# PR9020.net
KiCad netlist of a schematic drawn in EAGLE
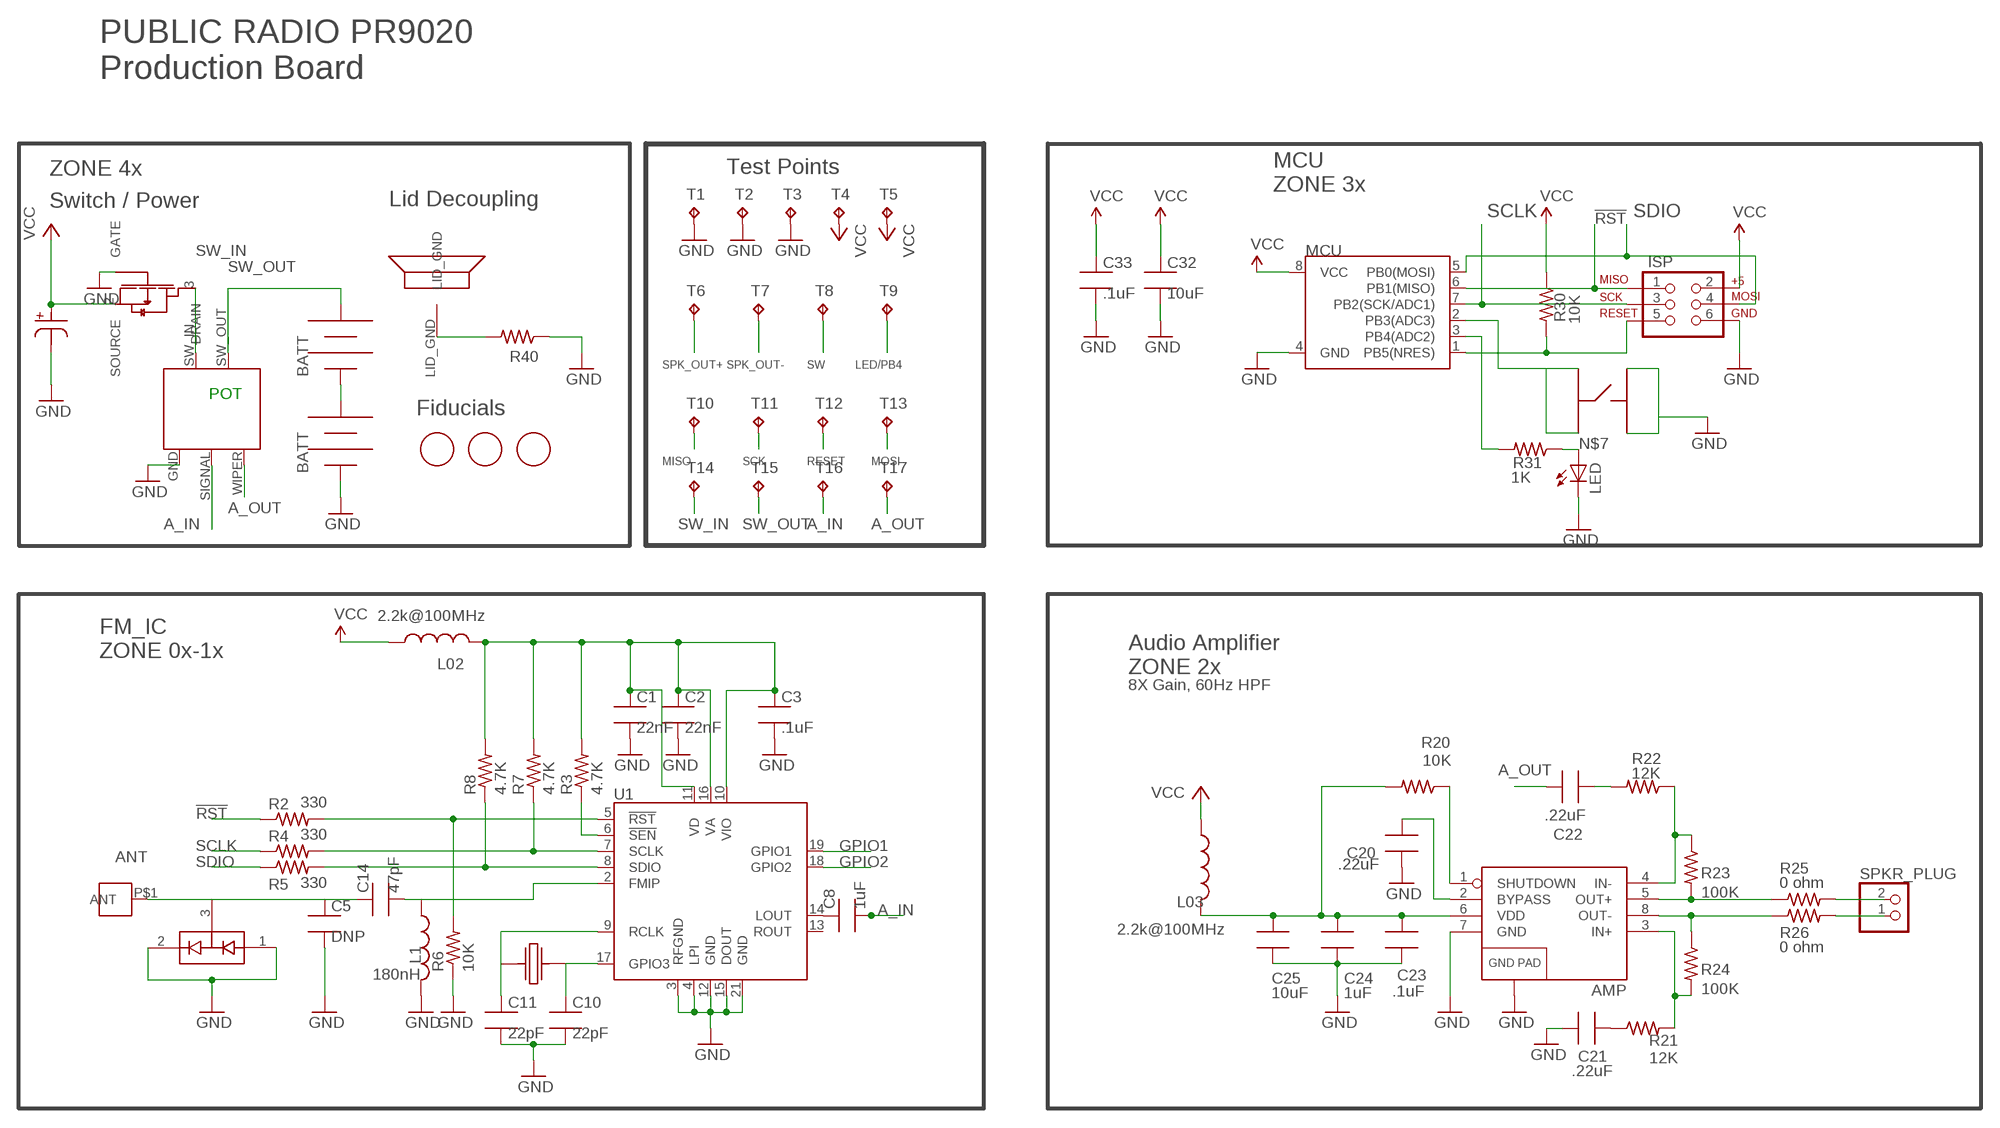
[diagram p0: schematic, sheet 1]

(export (version "E")
  (design (tool "Eeschema 10.0.6"))
  (components
    (comp (ref "AMP")
      (value "TPA6203A1")
      (footprint "eagle-import:8-MSOP")
      (libsource (lib "eagle-import") (part "TPA6203A1"))
    )
    (comp (ref "ANT_MOUNT")
      (value "DNP")
      (footprint "eagle-import:M3_BOLT_HOLE")
      (libsource (lib "eagle-import") (part "M3_SCREW_POST"))
    )
    (comp (ref "C1")
      (value "22nF")
      (footprint "eagle-import:0603_CPL")
      (fields
        (field (name "MFG_PN") "CL10B223KB8NNNC")
        (field (name "TOL") "10%")
        (field (name "VOLTAGE") "16V")
      )
      (libsource (lib "eagle-import") (part "C_SMT_0603_CPL"))
    )
    (comp (ref "C2")
      (value "22nF")
      (footprint "eagle-import:0603_CPL")
      (fields
        (field (name "MFG_PN") "CL10B223KB8NNNC")
        (field (name "TOL") "10%")
        (field (name "VOLTAGE") "16V")
      )
      (libsource (lib "eagle-import") (part "C_SMT_0603_CPL"))
    )
    (comp (ref "C3")
      (value ".1uF")
      (footprint "eagle-import:0603_CPL")
      (fields
        (field (name "MFG_PN") "CL10B104KB8SFNC")
        (field (name "TOL") "10%")
        (field (name "VOLTAGE") "16V")
      )
      (libsource (lib "eagle-import") (part "C_SMT_0603_CPL"))
    )
    (comp (ref "C5")
      (value "DNP")
      (footprint "eagle-import:0603_CPL")
      (fields (field (name "MFG_PN") "DNP") (field (name "TOL") "2%") (field (name "VOLTAGE") "50V"))
      (libsource (lib "eagle-import") (part "C_SMT_0603_CPL"))
    )
    (comp (ref "C8")
      (value "1uF")
      (footprint "eagle-import:0603_CPL")
      (fields
        (field (name "MFG_PN") "CL10B105KP8NNNC")
        (field (name "TOL") "10%")
        (field (name "VOLTAGE") "10V")
      )
      (libsource (lib "eagle-import") (part "C_SMT_0603_CPL"))
    )
    (comp (ref "C10")
      (value "22pF")
      (footprint "eagle-import:0603_CPL")
      (fields
        (field (name "MFG_PN") "C1608C0G1H220J080AA")
        (field (name "TOL") "5%")
        (field (name "VOLTAGE") "50V")
      )
      (libsource (lib "eagle-import") (part "C_SMT_0603_CPL"))
    )
    (comp (ref "C11")
      (value "22pF")
      (footprint "eagle-import:0603_CPL")
      (fields
        (field (name "MFG_PN") "C1608C0G1H220J080AA")
        (field (name "TOL") "5%")
        (field (name "VOLTAGE") "50V")
      )
      (libsource (lib "eagle-import") (part "C_SMT_0603_CPL"))
    )
    (comp (ref "C14")
      (value "47pF")
      (footprint "eagle-import:0603_CPL")
      (fields
        (field (name "MFG_PN") "CL10C470JB8NCNC")
        (field (name "TOL") "5%")
        (field (name "VOLTAGE") "50V")
      )
      (libsource (lib "eagle-import") (part "C_SMT_0603_CPL"))
    )
    (comp (ref "C20")
      (value ".22uF")
      (footprint "eagle-import:0603_CPL")
      (fields
        (field (name "MFG_PN") "C1608X7R1C224K080AC")
        (field (name "TOL") "10%")
        (field (name "VOLTAGE") "16V")
      )
      (libsource (lib "eagle-import") (part "C_SMT_0603_CPL"))
    )
    (comp (ref "C21")
      (value ".22uF")
      (footprint "eagle-import:0603_CPL")
      (fields
        (field (name "MFG_PN") "C1608X7R1C224K080AC")
        (field (name "TOL") "10%")
        (field (name "VOLTAGE") "16V")
      )
      (libsource (lib "eagle-import") (part "C_SMT_0603_CPL"))
    )
    (comp (ref "C22")
      (value ".22uF")
      (footprint "eagle-import:0603_CPL")
      (fields
        (field (name "MFG_PN") "C1608X7R1C224K080AC")
        (field (name "TOL") "10%")
        (field (name "VOLTAGE") "16V")
      )
      (libsource (lib "eagle-import") (part "C_SMT_0603_CPL"))
    )
    (comp (ref "C23")
      (value ".1uF")
      (footprint "eagle-import:0603_CPL")
      (fields
        (field (name "MFG_PN") "CL10B104KB8SFNC")
        (field (name "TOL") "10%")
        (field (name "VOLTAGE") "16V")
      )
      (libsource (lib "eagle-import") (part "C_SMT_0603_CPL"))
    )
    (comp (ref "C24")
      (value "1uF")
      (footprint "eagle-import:0603_CPL")
      (fields
        (field (name "MFG_PN") "CL10B105KP8NNNC")
        (field (name "TOL") "10%")
        (field (name "VOLTAGE") "10V")
      )
      (libsource (lib "eagle-import") (part "C_SMT_0603_CPL"))
    )
    (comp (ref "C25")
      (value "10uF")
      (footprint "eagle-import:0603_CPL")
      (fields
        (field (name "MFG_PN") "CL10A106MQ8NNNC")
        (field (name "TOL") "20%")
        (field (name "VOLTAGE") "6.3V")
      )
      (libsource (lib "eagle-import") (part "C_SMT_0603_CPL"))
    )
    (comp (ref "C32")
      (value "10uF")
      (footprint "eagle-import:0603_CPL")
      (fields
        (field (name "MFG_PN") "CL10A106MQ8NNNC")
        (field (name "TOL") "20%")
        (field (name "VOLTAGE") "6.3V")
      )
      (libsource (lib "eagle-import") (part "C_SMT_0603_CPL"))
    )
    (comp (ref "C33")
      (value ".1uF")
      (footprint "eagle-import:0603_CPL")
      (fields
        (field (name "MFG_PN") "CL10B104KB8SFNC")
        (field (name "TOL") "10%")
        (field (name "VOLTAGE") "16V")
      )
      (libsource (lib "eagle-import") (part "C_SMT_0603_CPL"))
    )
    (comp (ref "C40")
      (value "220uF")
      (footprint "eagle-import:NICHICON_UD_63")
      (fields (field (name "TOL") "20%") (field (name "VOLTAGE") "16V"))
      (libsource (lib "eagle-import") (part "NICHICON_SERIESUD"))
    )
    (comp (ref "D1")
      (value "BAV99")
      (footprint "eagle-import:SOT23_CPL")
      (fields (field (name "MFG_PN") "BAV99,215"))
      (libsource (lib "eagle-import") (part "BAV99"))
    )
    (comp (ref "FET1")
      (value "AO3435")
      (footprint "eagle-import:SOT23_CPL")
      (fields (field (name "MFG_PN") "AO3435"))
      (libsource (lib "eagle-import") (part "AO3435"))
    )
    (comp (ref "ISP")
      (value "AVR_SPI_PRG_6NS")
      (footprint "eagle-import:2X3-NS")
      (libsource (lib "eagle-import") (part "AVR_SPI_PRG_6NS"))
    )
    (comp (ref "JP5")
      (value "BK-92_MPD_AA_BATT_CLIP")
      (footprint "eagle-import:BK92_AA_BATT")
      (fields (field (name "MFG_PN") "2 of BK92 - supplied by CL Labs"))
      (libsource (lib "eagle-import") (part "BK-92_MPD_AA_BATT_CLIP"))
    )
    (comp (ref "JP6")
      (value "BK-92_MPD_AA_BATT_CLIP")
      (footprint "eagle-import:BK92_AA_BATT")
      (fields (field (name "MFG_PN") "2 of BK92 - supplied by CL Labs"))
      (libsource (lib "eagle-import") (part "BK-92_MPD_AA_BATT_CLIP"))
    )
    (comp (ref "L1")
      (value "180nH")
      (footprint "eagle-import:0805_ADAFRUIT")
      (fields
        (field (name "CURRENT") "400mA")
        (field (name "DCR") "640m")
        (field (name "MFG_PN") "AISC-0805-R18J-T")
        (field (name "TOL") "5%")
      )
      (libsource (lib "eagle-import") (part "L_SMT_0805_ADAFRUIT"))
    )
    (comp (ref "L02")
      (value "2.2k@100MHz")
      (footprint "eagle-import:0603_CPL")
      (fields
        (field (name "CURRENT") "150mA")
        (field (name "DCR") "2.3")
        (field (name "MFG_PN") "HZ0603A222R-10")
      )
      (libsource (lib "eagle-import") (part "L_SMT_0603_CPL"))
    )
    (comp (ref "L03")
      (value "2.2k@100MHz")
      (footprint "eagle-import:0603_CPL")
      (fields
        (field (name "CURRENT") "150mA")
        (field (name "DCR") "2.3")
        (field (name "MFG_PN") "HZ0603A222R-10")
      )
      (libsource (lib "eagle-import") (part "L_SMT_0603_CPL"))
    )
    (comp (ref "LED")
      (value "LEDCHIPLED_0805")
      (footprint "eagle-import:CHIPLED_0805")
      (libsource (lib "eagle-import") (part "LEDCHIPLED_0805"))
    )
    (comp (ref "MARK1")
      (value "FIDUCIAL")
      (footprint "eagle-import:FIDUCIAL_1MM")
      (libsource (lib "eagle-import") (part "FIDUCIAL"))
    )
    (comp (ref "MARK2")
      (value "FIDUCIAL")
      (footprint "eagle-import:FIDUCIAL_1MM")
      (libsource (lib "eagle-import") (part "FIDUCIAL"))
    )
    (comp (ref "MARK3")
      (value "FIDUCIAL")
      (footprint "eagle-import:FIDUCIAL_1MM")
      (libsource (lib "eagle-import") (part "FIDUCIAL"))
    )
    (comp (ref "MCU")
      (value "ATTINY45TINY45-20-SMT")
      (footprint "eagle-import:8-SOIC")
      (libsource (lib "eagle-import") (part "ATTINY45TINY45-20-SMT"))
    )
    (comp (ref "R1")
      (value "RV170SF_TAIWANA_POT_SW")
      (footprint "eagle-import:RV170SF_SW_POT")
      (fields (field (name "MFG_PN") "RV170SF-43-20F-A10K - supplied by CL Labs"))
      (libsource (lib "eagle-import") (part "RV170SF_TAIWANA_POT_SW"))
    )
    (comp (ref "R2")
      (value "330")
      (footprint "eagle-import:0603_CPL")
      (fields (field (name "MFG_PN") "MCR03ERTJ331") (field (name "POWER") "1/10W") (field (name "TOL") "5%"))
      (libsource (lib "eagle-import") (part "R_SMT_R0603_CPL"))
    )
    (comp (ref "R3")
      (value "4.7K")
      (footprint "eagle-import:0603_CPL")
      (fields
        (field (name "MFG_PN") "ERJ-3EKF4701V")
        (field (name "POWER") "1/10W")
        (field (name "TOL") "1%")
      )
      (libsource (lib "eagle-import") (part "R_SMT_R0603_CPL"))
    )
    (comp (ref "R4")
      (value "330")
      (footprint "eagle-import:0603_CPL")
      (fields (field (name "MFG_PN") "MCR03ERTJ331") (field (name "POWER") "1/10W") (field (name "TOL") "5%"))
      (libsource (lib "eagle-import") (part "R_SMT_R0603_CPL"))
    )
    (comp (ref "R5")
      (value "330")
      (footprint "eagle-import:0603_CPL")
      (fields (field (name "MFG_PN") "MCR03ERTJ331") (field (name "POWER") "1/10W") (field (name "TOL") "5%"))
      (libsource (lib "eagle-import") (part "R_SMT_R0603_CPL"))
    )
    (comp (ref "R6")
      (value "10K")
      (footprint "eagle-import:0603_CPL")
      (fields
        (field (name "MFG_PN") "ERJ-3GEYJ103V")
        (field (name "POWER") "1/10W")
        (field (name "TOL") "5%")
      )
      (libsource (lib "eagle-import") (part "R_SMT_R0603_CPL"))
    )
    (comp (ref "R7")
      (value "4.7K")
      (footprint "eagle-import:0603_CPL")
      (fields
        (field (name "MFG_PN") "ERJ-3EKF4701V")
        (field (name "POWER") "1/10W")
        (field (name "TOL") "1%")
      )
      (libsource (lib "eagle-import") (part "R_SMT_R0603_CPL"))
    )
    (comp (ref "R8")
      (value "4.7K")
      (footprint "eagle-import:0603_CPL")
      (fields
        (field (name "MFG_PN") "ERJ-3EKF4701V")
        (field (name "POWER") "1/10W")
        (field (name "TOL") "1%")
      )
      (libsource (lib "eagle-import") (part "R_SMT_R0603_CPL"))
    )
    (comp (ref "R20")
      (value "10K")
      (footprint "eagle-import:0603_CPL")
      (fields
        (field (name "MFG_PN") "ERJ-3GEYJ103V")
        (field (name "POWER") "1/10W")
        (field (name "TOL") "5%")
      )
      (libsource (lib "eagle-import") (part "R_SMT_R0603_CPL"))
    )
    (comp (ref "R21")
      (value "12K")
      (footprint "eagle-import:0603_CPL")
      (fields
        (field (name "MFG_PN") "RC0603FR-0712KL")
        (field (name "POWER") "1/10W")
        (field (name "TOL") "1%")
      )
      (libsource (lib "eagle-import") (part "R_SMT_R0603_CPL"))
    )
    (comp (ref "R22")
      (value "12K")
      (footprint "eagle-import:0603_CPL")
      (fields
        (field (name "MFG_PN") "RC0603FR-0712KL")
        (field (name "POWER") "1/10W")
        (field (name "TOL") "1%")
      )
      (libsource (lib "eagle-import") (part "R_SMT_R0603_CPL"))
    )
    (comp (ref "R23")
      (value "100K")
      (footprint "eagle-import:0603_CPL")
      (fields
        (field (name "MFG_PN") "ERJ-3EKF1003V")
        (field (name "POWER") "1/10W")
        (field (name "TOL") "1%")
      )
      (libsource (lib "eagle-import") (part "R_SMT_R0603_CPL"))
    )
    (comp (ref "R24")
      (value "100K")
      (footprint "eagle-import:0603_CPL")
      (fields
        (field (name "MFG_PN") "ERJ-3EKF1003V")
        (field (name "POWER") "1/10W")
        (field (name "TOL") "1%")
      )
      (libsource (lib "eagle-import") (part "R_SMT_R0603_CPL"))
    )
    (comp (ref "R25")
      (value "0 ohm")
      (footprint "eagle-import:0805_ADAFRUIT")
      (fields (field (name "MFG_PN") "ERJ-6GEY0R00V "))
      (libsource (lib "eagle-import") (part "R_SMT_0805_ADAFRUIT"))
    )
    (comp (ref "R26")
      (value "0 ohm")
      (footprint "eagle-import:0805_ADAFRUIT")
      (fields (field (name "MFG_PN") "ERJ-6GEY0R00V "))
      (libsource (lib "eagle-import") (part "R_SMT_0805_ADAFRUIT"))
    )
    (comp (ref "R30")
      (value "10K")
      (footprint "eagle-import:0603_CPL")
      (fields
        (field (name "MFG_PN") "ERJ-3GEYJ103V")
        (field (name "POWER") "1/10W")
        (field (name "TOL") "5%")
      )
      (libsource (lib "eagle-import") (part "R_SMT_R0603_CPL"))
    )
    (comp (ref "R31")
      (value "1K")
      (footprint "eagle-import:0603_CPL")
      (fields
        (field (name "MFG_PN") "ERJ-3EKF1001V")
        (field (name "POWER") "1/10W")
        (field (name "TOL") "1%")
      )
      (libsource (lib "eagle-import") (part "R_SMT_R0603_CPL"))
    )
    (comp (ref "R40")
      (value "DNP")
      (footprint "eagle-import:0603_CPL")
      (fields (field (name "MFG_PN") "ERJ-3GEY0R00V"))
      (libsource (lib "eagle-import") (part "R_SMT_R0603_CPL"))
    )
    (comp (ref "SPKR_PLACE")
      (value "DNP")
      (footprint "eagle-import:PR2023_SPKR_PLACE")
      (libsource (lib "eagle-import") (part "PR2023_SPKR"))
    )
    (comp (ref "SPKR_PLUG")
      (value "JST_2PIN-SMT-RA")
      (footprint "eagle-import:JST-B2B-PH-SM4-TB")
      (libsource (lib "eagle-import") (part "JST_2PIN-SMT-RA"))
    )
    (comp (ref "SW1")
      (value "C&K_PTS645")
      (footprint "eagle-import:C&K_PTS645_SMT")
      (libsource (lib "eagle-import") (part "C&K_PTS645"))
    )
    (comp (ref "T1")
      (value "TPTP20R")
      (footprint "eagle-import:TP20R")
      (libsource (lib "eagle-import") (part "TPTP20R"))
    )
    (comp (ref "T2")
      (value "TPTP20R")
      (footprint "eagle-import:TP20R")
      (libsource (lib "eagle-import") (part "TPTP20R"))
    )
    (comp (ref "T3")
      (value "TPTP20R")
      (footprint "eagle-import:TP20R")
      (libsource (lib "eagle-import") (part "TPTP20R"))
    )
    (comp (ref "T4")
      (value "TPTP20R")
      (footprint "eagle-import:TP20R")
      (libsource (lib "eagle-import") (part "TPTP20R"))
    )
    (comp (ref "T5")
      (value "TPTP20R")
      (footprint "eagle-import:TP20R")
      (libsource (lib "eagle-import") (part "TPTP20R"))
    )
    (comp (ref "T6")
      (value "TPTP20R")
      (footprint "eagle-import:TP20R")
      (libsource (lib "eagle-import") (part "TPTP20R"))
    )
    (comp (ref "T7")
      (value "TPTP20R")
      (footprint "eagle-import:TP20R")
      (libsource (lib "eagle-import") (part "TPTP20R"))
    )
    (comp (ref "T8")
      (value "TPTP20R")
      (footprint "eagle-import:TP20R")
      (libsource (lib "eagle-import") (part "TPTP20R"))
    )
    (comp (ref "T9")
      (value "TPTP20R")
      (footprint "eagle-import:TP20R")
      (libsource (lib "eagle-import") (part "TPTP20R"))
    )
    (comp (ref "T10")
      (value "TPTP20R")
      (footprint "eagle-import:TP20R")
      (libsource (lib "eagle-import") (part "TPTP20R"))
    )
    (comp (ref "T11")
      (value "TPTP20R")
      (footprint "eagle-import:TP20R")
      (libsource (lib "eagle-import") (part "TPTP20R"))
    )
    (comp (ref "T12")
      (value "TPTP20R")
      (footprint "eagle-import:TP20R")
      (libsource (lib "eagle-import") (part "TPTP20R"))
    )
    (comp (ref "T13")
      (value "TPTP20R")
      (footprint "eagle-import:TP20R")
      (libsource (lib "eagle-import") (part "TPTP20R"))
    )
    (comp (ref "T14")
      (value "TPTP20R")
      (footprint "eagle-import:TP20R")
      (libsource (lib "eagle-import") (part "TPTP20R"))
    )
    (comp (ref "T15")
      (value "TPTP20R")
      (footprint "eagle-import:TP20R")
      (libsource (lib "eagle-import") (part "TPTP20R"))
    )
    (comp (ref "T16")
      (value "TPTP20R")
      (footprint "eagle-import:TP20R")
      (libsource (lib "eagle-import") (part "TPTP20R"))
    )
    (comp (ref "T17")
      (value "TPTP20R")
      (footprint "eagle-import:TP20R")
      (libsource (lib "eagle-import") (part "TPTP20R"))
    )
    (comp (ref "U1")
      (value "SI4702-C19-GMR")
      (footprint "eagle-import:SI470X_20_QFN")
      (fields (field (name "MFG_PN") "Si4702 C19 GM - supplied by CL Labs"))
      (libsource (lib "eagle-import") (part "SI4702-C19-GMR"))
    )
    (comp (ref "X1")
      (value "ABS25XTAL")
      (footprint "eagle-import:4-SOJ")
      (libsource (lib "eagle-import") (part "ABS25XTAL"))
    )
  )
  (nets
    (net (code "1") (name "/ANT") (class "Default")
      (node (ref "ANT_MOUNT") (pin "P$1") (pinfunction "ANT_P$1") (pintype "bidirectional"))
      (node (ref "C14") (pin "1") (pinfunction "1_1") (pintype "passive"))
      (node (ref "C5") (pin "1") (pinfunction "1_1") (pintype "passive"))
      (node (ref "D1") (pin "3") (pinfunction "COM_3") (pintype "bidirectional"))
    )
    (net (code "2") (name "/A_IN") (class "Default")
      (node (ref "C8") (pin "2") (pinfunction "2_2") (pintype "passive"))
      (node (ref "R1") (pin "SIGNAL") (pinfunction "SIGNAL_SIGNAL") (pintype "bidirectional"))
      (node (ref "T16") (pin "TP") (pinfunction "TP_TP") (pintype "input"))
    )
    (net (code "3") (name "/A_OUT") (class "Default")
      (node (ref "C22") (pin "2") (pinfunction "2_2") (pintype "passive"))
      (node (ref "R1") (pin "WIPER") (pinfunction "WIPER_WIPER") (pintype "bidirectional"))
      (node (ref "T17") (pin "TP") (pinfunction "TP_TP") (pintype "input"))
    )
    (net (code "4") (name "/GPIO1") (class "Default")
      (node (ref "U1") (pin "19") (pinfunction "GPIO1_19") (pintype "bidirectional"))
    )
    (net (code "5") (name "/GPIO2") (class "Default")
      (node (ref "U1") (pin "18") (pinfunction "GPIO2_18") (pintype "bidirectional"))
    )
    (net (code "6") (name "/LED{slash}PB4") (class "Default")
      (node (ref "MCU") (pin "3") (pinfunction "PB4(ADC2)_3") (pintype "bidirectional"))
      (node (ref "R31") (pin "2") (pinfunction "2_2") (pintype "passive"))
      (node (ref "T9") (pin "TP") (pinfunction "TP_TP") (pintype "input"))
    )
    (net (code "7") (name "/N$7") (class "Default")
      (node (ref "LED") (pin "A") (pinfunction "A_A") (pintype "passive"))
      (node (ref "R31") (pin "1") (pinfunction "1_1") (pintype "passive"))
    )
    (net (code "8") (name "/RESET") (class "Default")
      (node (ref "ISP") (pin "5") (pinfunction "5_5") (pintype "passive"))
      (node (ref "MCU") (pin "1") (pinfunction "PB5(NRES)_1") (pintype "bidirectional"))
      (node (ref "R30") (pin "2") (pinfunction "2_2") (pintype "passive"))
      (node (ref "T12") (pin "TP") (pinfunction "TP_TP") (pintype "input"))
    )
    (net (code "9") (name "/SCLK") (class "Default")
      (node (ref "ISP") (pin "3") (pinfunction "3_3") (pintype "passive"))
      (node (ref "MCU") (pin "7") (pinfunction "PB2(SCK/ADC1)_7") (pintype "bidirectional"))
      (node (ref "R4") (pin "1") (pinfunction "1_1") (pintype "passive"))
      (node (ref "T11") (pin "TP") (pinfunction "TP_TP") (pintype "input"))
    )
    (net (code "10") (name "/SDIO") (class "Default")
      (node (ref "ISP") (pin "4") (pinfunction "4_4") (pintype "passive"))
      (node (ref "MCU") (pin "5") (pinfunction "PB0(MOSI)_5") (pintype "bidirectional"))
      (node (ref "R5") (pin "1") (pinfunction "1_1") (pintype "passive"))
      (node (ref "T13") (pin "TP") (pinfunction "TP_TP") (pintype "input"))
    )
    (net (code "11") (name "/SPK_OUT+") (class "Default")
      (node (ref "R25") (pin "2") (pinfunction "2_2") (pintype "passive"))
      (node (ref "SPKR_PLUG") (pin "2") (pinfunction "1_2") (pintype "passive"))
      (node (ref "T6") (pin "TP") (pinfunction "TP_TP") (pintype "input"))
    )
    (net (code "12") (name "/SPK_OUT-") (class "Default")
      (node (ref "R26") (pin "2") (pinfunction "2_2") (pintype "passive"))
      (node (ref "SPKR_PLUG") (pin "1") (pinfunction "2_1") (pintype "passive"))
      (node (ref "T7") (pin "TP") (pinfunction "TP_TP") (pintype "input"))
    )
    (net (code "13") (name "/SW") (class "Default")
      (node (ref "MCU") (pin "2") (pinfunction "PB3(ADC3)_2") (pintype "bidirectional"))
      (node (ref "SW1") (pin "P$3") (pinfunction "P$3_P$3") (pintype "bidirectional"))
      (node (ref "SW1") (pin "P$4") (pinfunction "P$4_P$4") (pintype "bidirectional"))
      (node (ref "T8") (pin "TP") (pinfunction "TP_TP") (pintype "input"))
    )
    (net (code "14") (name "/SW_IN") (class "Default")
      (node (ref "FET1") (pin "3") (pinfunction "DRAIN_3") (pintype "bidirectional"))
      (node (ref "R1") (pin "SW_IN") (pinfunction "SW_IN_SW_IN") (pintype "bidirectional"))
      (node (ref "T14") (pin "TP") (pinfunction "TP_TP") (pintype "input"))
    )
    (net (code "15") (name "/SW_OUT") (class "Default")
      (node (ref "JP5") (pin "POS") (pinfunction "POS_POS") (pintype "bidirectional"))
      (node (ref "JP5") (pin "POS@2") (pinfunction "POS_POS@2") (pintype "bidirectional"))
      (node (ref "R1") (pin "SW_OUT") (pinfunction "SW_OUT_SW_OUT") (pintype "bidirectional"))
      (node (ref "T15") (pin "TP") (pinfunction "TP_TP") (pintype "input"))
    )
    (net (code "16") (name "/~{RST}") (class "Default")
      (node (ref "ISP") (pin "1") (pinfunction "1_1") (pintype "passive"))
      (node (ref "MCU") (pin "6") (pinfunction "PB1(MISO)_6") (pintype "bidirectional"))
      (node (ref "R2") (pin "1") (pinfunction "1_1") (pintype "passive"))
      (node (ref "T10") (pin "TP") (pinfunction "TP_TP") (pintype "input"))
    )
    (net (code "17") (name "GND") (class "Default")
      (node (ref "AMP") (pin "7") (pinfunction "GND_7") (pintype "power_in"))
      (node (ref "AMP") (pin "9") (pinfunction "GND_9") (pintype "power_in"))
      (node (ref "C1") (pin "2") (pinfunction "2_2") (pintype "passive"))
      (node (ref "C10") (pin "2") (pinfunction "2_2") (pintype "passive"))
      (node (ref "C11") (pin "2") (pinfunction "2_2") (pintype "passive"))
      (node (ref "C2") (pin "2") (pinfunction "2_2") (pintype "passive"))
      (node (ref "C20") (pin "1") (pinfunction "1_1") (pintype "passive"))
      (node (ref "C21") (pin "1") (pinfunction "1_1") (pintype "passive"))
      (node (ref "C23") (pin "2") (pinfunction "2_2") (pintype "passive"))
      (node (ref "C24") (pin "2") (pinfunction "2_2") (pintype "passive"))
      (node (ref "C25") (pin "2") (pinfunction "2_2") (pintype "passive"))
      (node (ref "C3") (pin "2") (pinfunction "2_2") (pintype "passive"))
      (node (ref "C32") (pin "2") (pinfunction "2_2") (pintype "passive"))
      (node (ref "C33") (pin "2") (pinfunction "2_2") (pintype "passive"))
      (node (ref "C40") (pin "P$2") (pinfunction "P$2_P$2") (pintype "bidirectional"))
      (node (ref "C5") (pin "2") (pinfunction "2_2") (pintype "passive"))
      (node (ref "D1") (pin "1") (pinfunction "A1_1") (pintype "bidirectional"))
      (node (ref "D1") (pin "2") (pinfunction "C2_2") (pintype "bidirectional"))
      (node (ref "FET1") (pin "1") (pinfunction "GATE_1") (pintype "bidirectional"))
      (node (ref "ISP") (pin "6") (pinfunction "6_6") (pintype "passive"))
      (node (ref "JP6") (pin "NEG") (pinfunction "NEG_NEG") (pintype "bidirectional"))
      (node (ref "JP6") (pin "NEG@2") (pinfunction "NEG_NEG@2") (pintype "bidirectional"))
      (node (ref "L1") (pin "2") (pinfunction "2_2") (pintype "passive"))
      (node (ref "LED") (pin "C") (pinfunction "C_C") (pintype "passive"))
      (node (ref "MCU") (pin "4") (pinfunction "GND_4") (pintype "bidirectional"))
      (node (ref "R1") (pin "GND") (pinfunction "GND_GND") (pintype "bidirectional"))
      (node (ref "R40") (pin "1") (pinfunction "1_1") (pintype "passive"))
      (node (ref "R6") (pin "1") (pinfunction "1_1") (pintype "passive"))
      (node (ref "SW1") (pin "P$1") (pinfunction "P$1_P$1") (pintype "bidirectional"))
      (node (ref "SW1") (pin "P$2") (pinfunction "P$2_P$2") (pintype "bidirectional"))
      (node (ref "T1") (pin "TP") (pinfunction "TP_TP") (pintype "input"))
      (node (ref "T2") (pin "TP") (pinfunction "TP_TP") (pintype "input"))
      (node (ref "T3") (pin "TP") (pinfunction "TP_TP") (pintype "input"))
      (node (ref "U1") (pin "12") (pinfunction "GND_12") (pintype "bidirectional"))
      (node (ref "U1") (pin "15") (pinfunction "DOUT_15") (pintype "bidirectional"))
      (node (ref "U1") (pin "21") (pinfunction "GND_21") (pintype "bidirectional"))
      (node (ref "U1") (pin "3") (pinfunction "RFGND_3") (pintype "bidirectional"))
      (node (ref "U1") (pin "4") (pinfunction "LPI_4") (pintype "bidirectional"))
    )
    (net (code "18") (name "Net-(AMP-BYPASS)") (class "Default")
      (node (ref "AMP") (pin "2") (pinfunction "BYPASS_2") (pintype "bidirectional"))
      (node (ref "C20") (pin "2") (pinfunction "2_2") (pintype "passive"))
    )
    (net (code "19") (name "Net-(AMP-IN+)") (class "Default")
      (node (ref "AMP") (pin "3") (pinfunction "IN+_3") (pintype "bidirectional"))
      (node (ref "R21") (pin "2") (pinfunction "2_2") (pintype "passive"))
      (node (ref "R24") (pin "2") (pinfunction "2_2") (pintype "passive"))
    )
    (net (code "20") (name "Net-(AMP-IN-)") (class "Default")
      (node (ref "AMP") (pin "4") (pinfunction "IN-_4") (pintype "bidirectional"))
      (node (ref "R22") (pin "1") (pinfunction "1_1") (pintype "passive"))
      (node (ref "R23") (pin "1") (pinfunction "1_1") (pintype "passive"))
    )
    (net (code "21") (name "Net-(AMP-OUT+)") (class "Default")
      (node (ref "AMP") (pin "5") (pinfunction "OUT+_5") (pintype "bidirectional"))
      (node (ref "R23") (pin "2") (pinfunction "2_2") (pintype "passive"))
      (node (ref "R25") (pin "1") (pinfunction "1_1") (pintype "passive"))
    )
    (net (code "22") (name "Net-(AMP-OUT-)") (class "Default")
      (node (ref "AMP") (pin "8") (pinfunction "OUT-_8") (pintype "bidirectional"))
      (node (ref "R24") (pin "1") (pinfunction "1_1") (pintype "passive"))
      (node (ref "R26") (pin "1") (pinfunction "1_1") (pintype "passive"))
    )
    (net (code "23") (name "Net-(AMP-SHUTDOWN)") (class "Default")
      (node (ref "AMP") (pin "1") (pinfunction "SHUTDOWN_1") (pintype "input"))
      (node (ref "R20") (pin "1") (pinfunction "1_1") (pintype "passive"))
    )
    (net (code "24") (name "Net-(AMP-VDD)") (class "Default")
      (node (ref "AMP") (pin "6") (pinfunction "VDD_6") (pintype "power_in"))
      (node (ref "C23") (pin "1") (pinfunction "1_1") (pintype "passive"))
      (node (ref "C24") (pin "1") (pinfunction "1_1") (pintype "passive"))
      (node (ref "C25") (pin "1") (pinfunction "1_1") (pintype "passive"))
      (node (ref "L03") (pin "2") (pinfunction "2_2") (pintype "passive"))
      (node (ref "R20") (pin "2") (pinfunction "2_2") (pintype "passive"))
    )
    (net (code "25") (name "Net-(C21-Pad2)") (class "Default")
      (node (ref "C21") (pin "2") (pinfunction "2_2") (pintype "passive"))
      (node (ref "R21") (pin "1") (pinfunction "1_1") (pintype "passive"))
    )
    (net (code "26") (name "Net-(C22-Pad1)") (class "Default")
      (node (ref "C22") (pin "1") (pinfunction "1_1") (pintype "passive"))
      (node (ref "R22") (pin "2") (pinfunction "2_2") (pintype "passive"))
    )
    (net (code "27") (name "Net-(JP5-NEG-PadNEG@2)") (class "Default")
      (node (ref "JP5") (pin "NEG") (pinfunction "NEG_NEG") (pintype "bidirectional"))
      (node (ref "JP5") (pin "NEG@2") (pinfunction "NEG_NEG@2") (pintype "bidirectional"))
      (node (ref "JP6") (pin "POS") (pinfunction "POS_POS") (pintype "bidirectional"))
      (node (ref "JP6") (pin "POS@2") (pinfunction "POS_POS@2") (pintype "bidirectional"))
    )
    (net (code "28") (name "Net-(R40-Pad2)") (class "Default")
      (node (ref "R40") (pin "2") (pinfunction "2_2") (pintype "passive"))
      (node (ref "SPKR_PLACE") (pin "LID_GND") (pinfunction "LID_GND_LID_GND") (pintype "bidirectional"))
    )
    (net (code "29") (name "Net-(U1-FMIP)") (class "Default")
      (node (ref "C14") (pin "2") (pinfunction "2_2") (pintype "passive"))
      (node (ref "L1") (pin "1") (pinfunction "1_1") (pintype "passive"))
      (node (ref "U1") (pin "2") (pinfunction "FMIP_2") (pintype "bidirectional"))
    )
    (net (code "30") (name "Net-(U1-GPIO3)") (class "Default")
      (node (ref "C10") (pin "1") (pinfunction "1_1") (pintype "passive"))
      (node (ref "U1") (pin "17") (pinfunction "GPIO3_17") (pintype "bidirectional"))
      (node (ref "X1") (pin "P$4") (pinfunction "P$4_P$4") (pintype "bidirectional"))
    )
    (net (code "31") (name "Net-(U1-LOUT)") (class "Default")
      (node (ref "C8") (pin "1") (pinfunction "1_1") (pintype "passive"))
      (node (ref "U1") (pin "14") (pinfunction "LOUT_14") (pintype "bidirectional"))
    )
    (net (code "32") (name "Net-(U1-RCLK)") (class "Default")
      (node (ref "C11") (pin "1") (pinfunction "1_1") (pintype "passive"))
      (node (ref "U1") (pin "9") (pinfunction "RCLK_9") (pintype "bidirectional"))
      (node (ref "X1") (pin "P$1") (pinfunction "P$1_P$1") (pintype "bidirectional"))
    )
    (net (code "33") (name "Net-(U1-SCLK)") (class "Default")
      (node (ref "R4") (pin "2") (pinfunction "2_2") (pintype "passive"))
      (node (ref "R7") (pin "1") (pinfunction "1_1") (pintype "passive"))
      (node (ref "U1") (pin "7") (pinfunction "SCLK_7") (pintype "bidirectional"))
    )
    (net (code "34") (name "Net-(U1-SDIO)") (class "Default")
      (node (ref "R5") (pin "2") (pinfunction "2_2") (pintype "passive"))
      (node (ref "R8") (pin "1") (pinfunction "1_1") (pintype "passive"))
      (node (ref "U1") (pin "8") (pinfunction "SDIO_8") (pintype "bidirectional"))
    )
    (net (code "35") (name "Net-(U1-VA)") (class "Default")
      (node (ref "C1") (pin "1") (pinfunction "1_1") (pintype "passive"))
      (node (ref "C2") (pin "1") (pinfunction "1_1") (pintype "passive"))
      (node (ref "C3") (pin "1") (pinfunction "1_1") (pintype "passive"))
      (node (ref "L02") (pin "2") (pinfunction "2_2") (pintype "passive"))
      (node (ref "R3") (pin "2") (pinfunction "2_2") (pintype "passive"))
      (node (ref "R7") (pin "2") (pinfunction "2_2") (pintype "passive"))
      (node (ref "R8") (pin "2") (pinfunction "2_2") (pintype "passive"))
      (node (ref "U1") (pin "10") (pinfunction "VIO_10") (pintype "bidirectional"))
      (node (ref "U1") (pin "11") (pinfunction "VD_11") (pintype "bidirectional"))
      (node (ref "U1") (pin "16") (pinfunction "VA_16") (pintype "bidirectional"))
    )
    (net (code "36") (name "Net-(U1-~{RST})") (class "Default")
      (node (ref "R2") (pin "2") (pinfunction "2_2") (pintype "passive"))
      (node (ref "R6") (pin "2") (pinfunction "2_2") (pintype "passive"))
      (node (ref "U1") (pin "5") (pinfunction "~{RST}_5") (pintype "bidirectional"))
    )
    (net (code "37") (name "Net-(U1-~{SEN})") (class "Default")
      (node (ref "R3") (pin "1") (pinfunction "1_1") (pintype "passive"))
      (node (ref "U1") (pin "6") (pinfunction "~{SEN}_6") (pintype "bidirectional"))
    )
    (net (code "38") (name "VCC") (class "Default")
      (node (ref "C32") (pin "1") (pinfunction "1_1") (pintype "passive"))
      (node (ref "C33") (pin "1") (pinfunction "1_1") (pintype "passive"))
      (node (ref "C40") (pin "P$1") (pinfunction "P$1_P$1") (pintype "bidirectional"))
      (node (ref "FET1") (pin "2") (pinfunction "SOURCE_2") (pintype "bidirectional"))
      (node (ref "ISP") (pin "2") (pinfunction "2_2") (pintype "passive"))
      (node (ref "L02") (pin "1") (pinfunction "1_1") (pintype "passive"))
      (node (ref "L03") (pin "1") (pinfunction "1_1") (pintype "passive"))
      (node (ref "MCU") (pin "8") (pinfunction "VCC_8") (pintype "bidirectional"))
      (node (ref "R30") (pin "1") (pinfunction "1_1") (pintype "passive"))
      (node (ref "T4") (pin "TP") (pinfunction "TP_TP") (pintype "input"))
      (node (ref "T5") (pin "TP") (pinfunction "TP_TP") (pintype "input"))
    )
    (net (code "39") (name "unconnected-(U1-ROUT-Pad13)") (class "Default")
      (node (ref "U1") (pin "13") (pinfunction "ROUT_13") (pintype "bidirectional"))
    )
  )
)
